# Shiva_Raken_Dahlevi.net
KiCad netlist of a schematic drawn in EAGLE
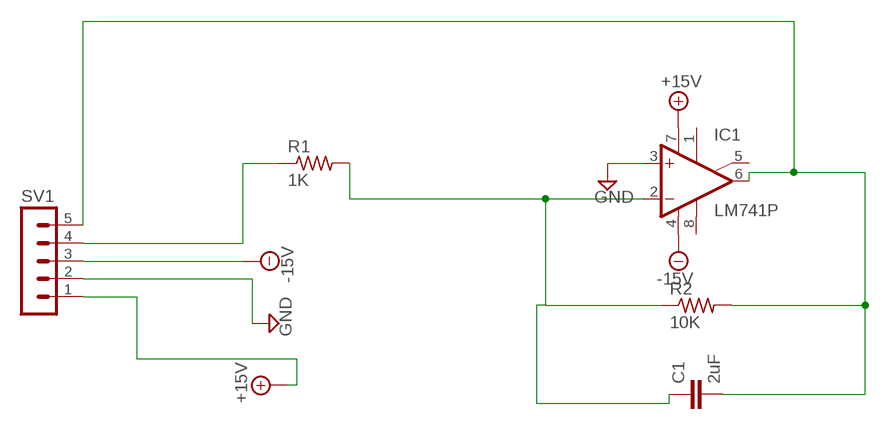
[diagram p0: schematic, sheet 1]

(export (version "E")
  (design (tool "Eeschema 10.0.6"))
  (components
    (comp (ref "C1")
      (value "2uF")
      (footprint "eagle-import:C0603")
      (libsource (lib "eagle-import") (part "C-EUC0603"))
    )
    (comp (ref "IC1")
      (value "LM741P")
      (footprint "eagle-import:DIL08")
      (libsource (lib "eagle-import") (part "741PLM"))
    )
    (comp (ref "R1")
      (value "1K")
      (footprint "eagle-import:R0603")
      (libsource (lib "eagle-import") (part "R-US_R0603"))
    )
    (comp (ref "R2")
      (value "10K")
      (footprint "eagle-import:R0603")
      (libsource (lib "eagle-import") (part "R-US_R0603"))
    )
    (comp (ref "SV1")
      (value "MA05-1")
      (footprint "eagle-import:MA05-1")
      (libsource (lib "eagle-import") (part "MA05-1"))
    )
  )
  (nets
    (net (code "1") (name "+15V") (class "Default")
      (node (ref "IC1") (pin "7") (pinfunction "V+_7") (pintype "power_in"))
      (node (ref "SV1") (pin "1") (pinfunction "1_1") (pintype "passive"))
    )
    (net (code "2") (name "-15V") (class "Default")
      (node (ref "IC1") (pin "4") (pinfunction "V-_4") (pintype "power_in"))
      (node (ref "SV1") (pin "3") (pinfunction "3_3") (pintype "passive"))
    )
    (net (code "3") (name "GND") (class "Default")
      (node (ref "IC1") (pin "3") (pinfunction "+IN_3") (pintype "input"))
      (node (ref "SV1") (pin "2") (pinfunction "2_2") (pintype "passive"))
    )
    (net (code "4") (name "Net-(IC1--IN)") (class "Default")
      (node (ref "C1") (pin "1") (pinfunction "1_1") (pintype "passive"))
      (node (ref "IC1") (pin "2") (pinfunction "-IN_2") (pintype "input"))
      (node (ref "R1") (pin "2") (pinfunction "2_2") (pintype "passive"))
      (node (ref "R2") (pin "1") (pinfunction "1_1") (pintype "passive"))
    )
    (net (code "5") (name "Net-(IC1-OUT)") (class "Default")
      (node (ref "C1") (pin "2") (pinfunction "2_2") (pintype "passive"))
      (node (ref "IC1") (pin "6") (pinfunction "OUT_6") (pintype "output"))
      (node (ref "R2") (pin "2") (pinfunction "2_2") (pintype "passive"))
      (node (ref "SV1") (pin "5") (pinfunction "5_5") (pintype "passive"))
    )
    (net (code "6") (name "Net-(R1-Pad1)") (class "Default")
      (node (ref "R1") (pin "1") (pinfunction "1_1") (pintype "passive"))
      (node (ref "SV1") (pin "4") (pinfunction "4_4") (pintype "passive"))
    )
    (net (code "7") (name "unconnected-(IC1-ON1-Pad1)") (class "Default")
      (node (ref "IC1") (pin "1") (pinfunction "ON1_1") (pintype "passive"))
    )
    (net (code "8") (name "unconnected-(IC1-ON2-Pad5)") (class "Default")
      (node (ref "IC1") (pin "5") (pinfunction "ON2_5") (pintype "passive"))
    )
    (net (code "9") (name "unconnected-(IC1-OPT-Pad8)") (class "Default")
      (node (ref "IC1") (pin "8") (pinfunction "OPT_8") (pintype "passive"))
    )
  )
)
